# Custom_Made_ESP32_by_Siam_V2.net
KiCad netlist of a schematic drawn in EasyEDA
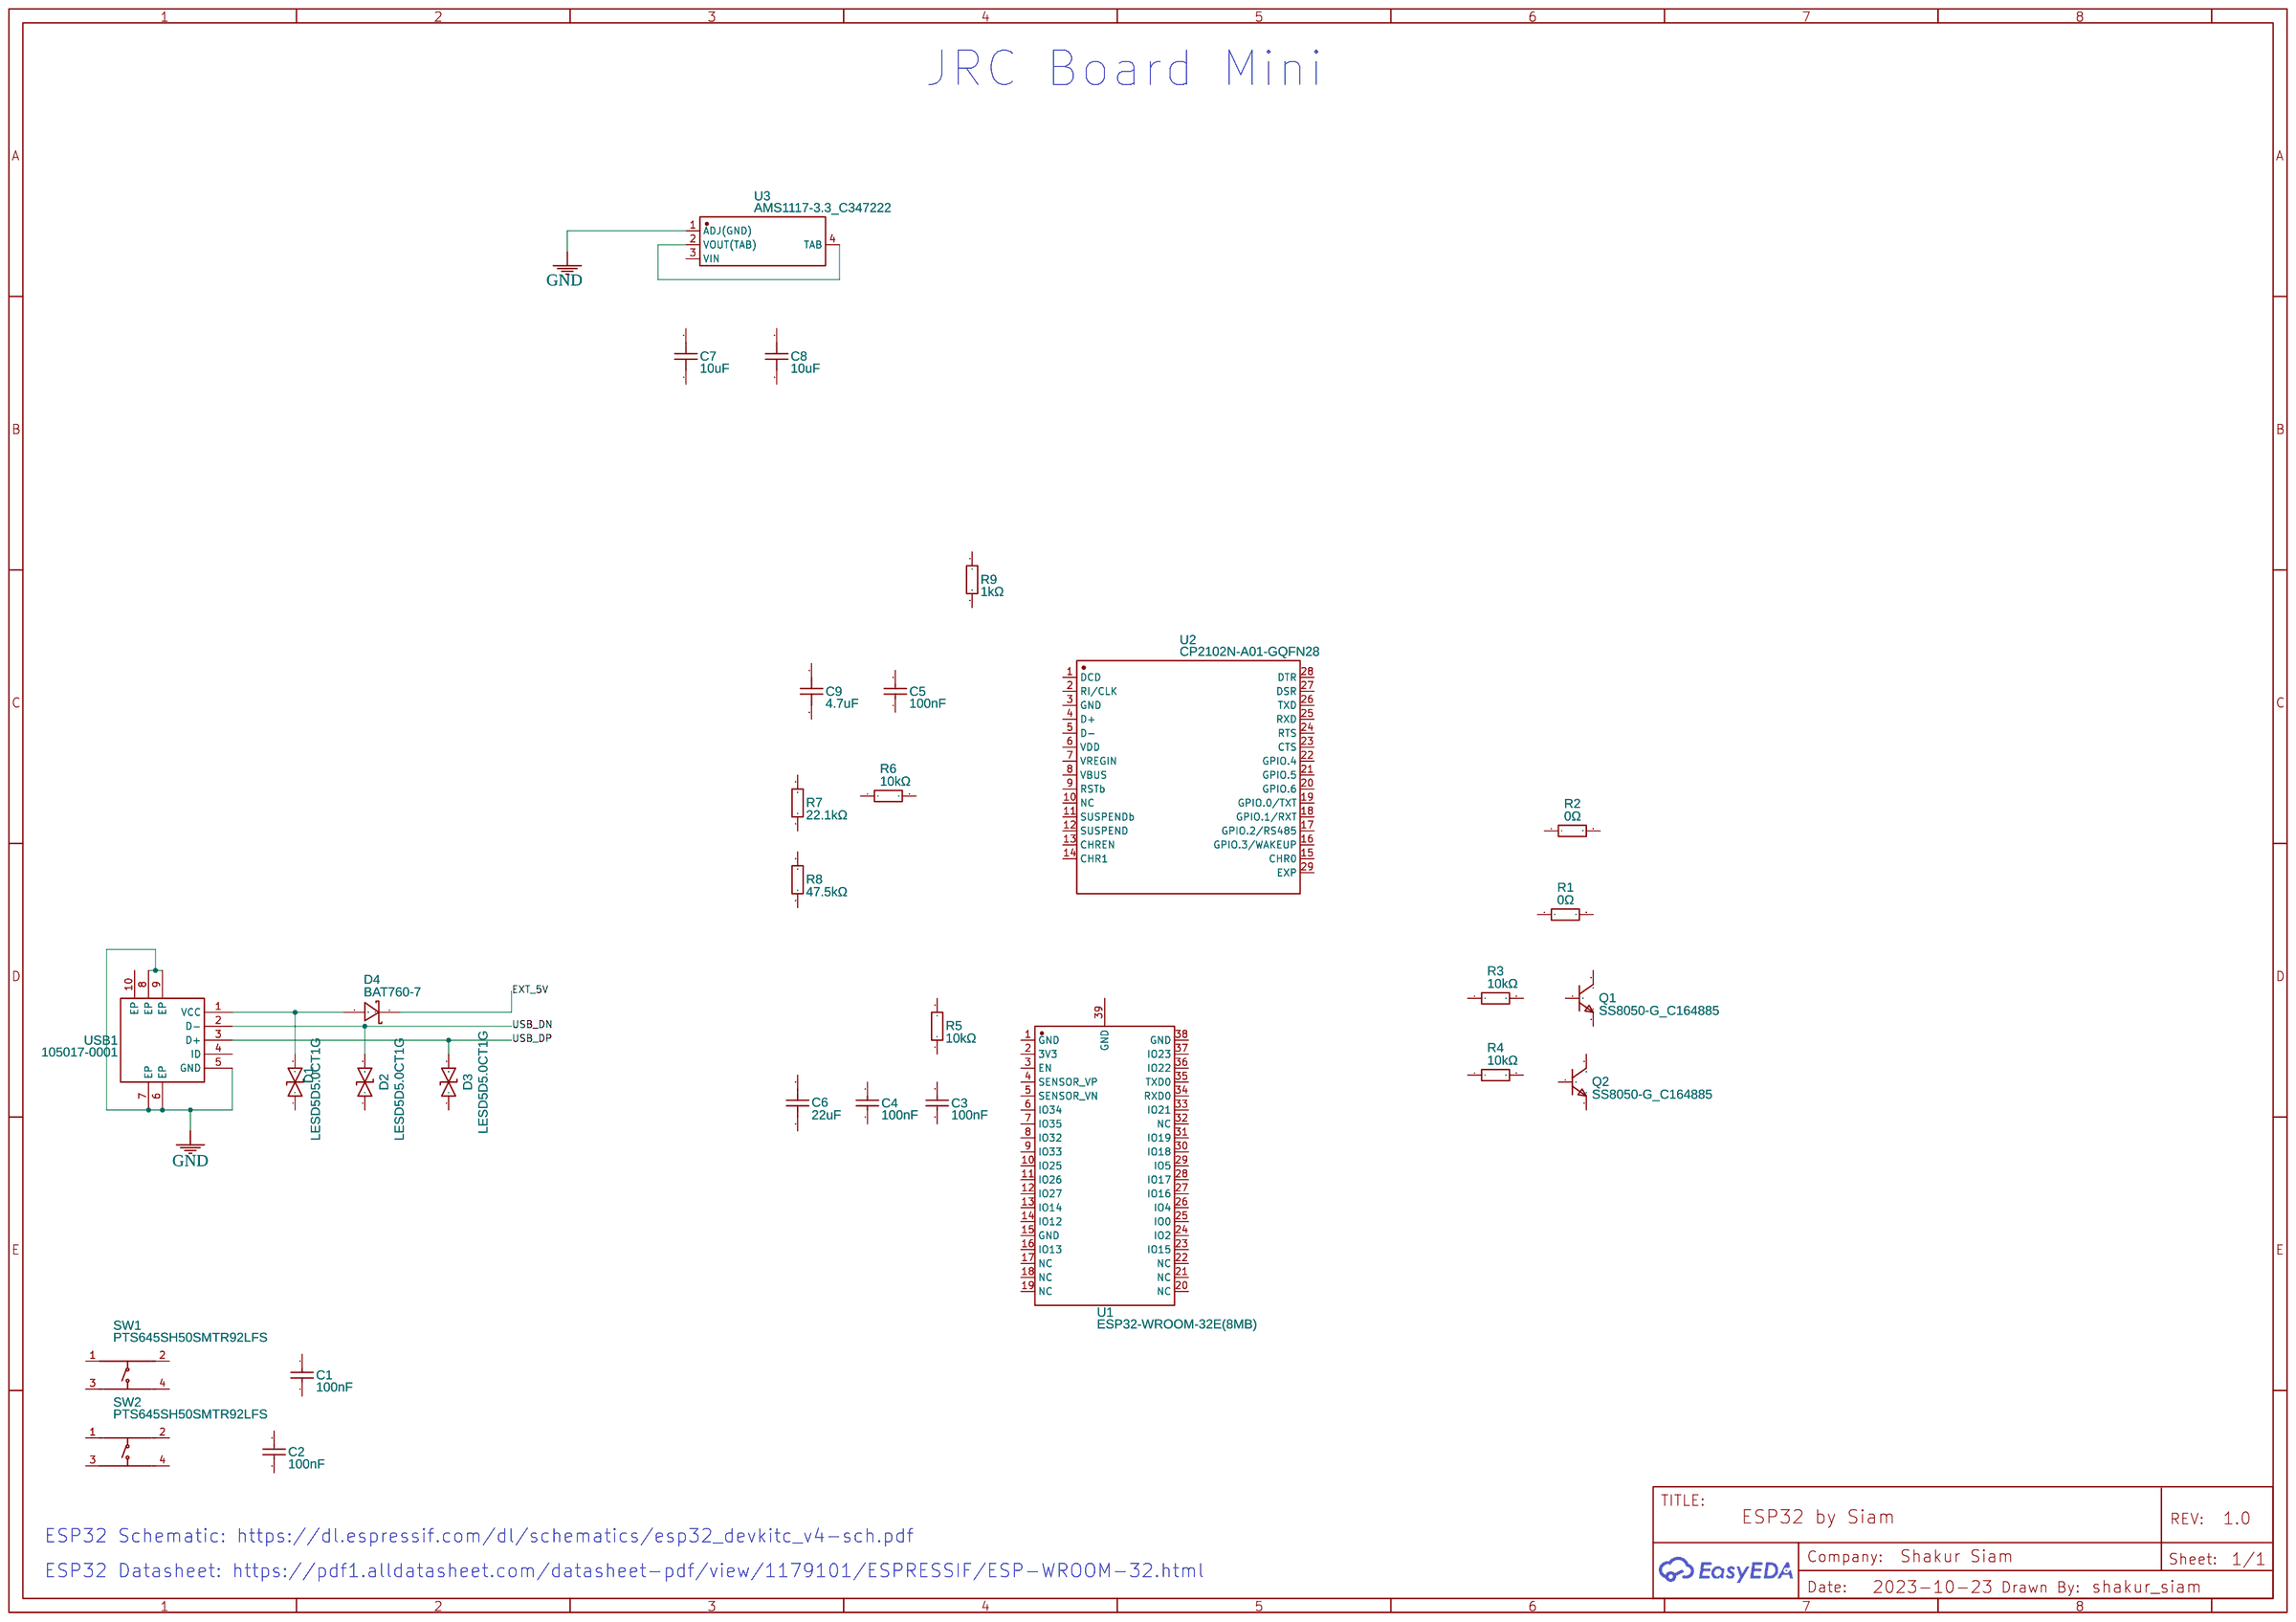
[diagram p0: schematic sheet]

(export (version "E")
  (design (tool "Eeschema 10.0.6"))
  (components
    (comp (ref "C1")
      (value "100nF")
      (fields
        (field (name "Manufacturer Part") "CL05B104KO5NNNC")
        (field (name "Manufacturer") "SAMSUNG(三星)")
      )
      (libsource (lib "") (part "CL05B104KO5NNNC"))
    )
    (comp (ref "C2")
      (value "100nF")
      (fields
        (field (name "Manufacturer Part") "CL05B104KO5NNNC")
        (field (name "Manufacturer") "SAMSUNG(三星)")
      )
      (libsource (lib "") (part "CL05B104KO5NNNC"))
    )
    (comp (ref "C3")
      (value "100nF")
      (fields
        (field (name "Manufacturer Part") "CL05B104KO5NNNC")
        (field (name "Manufacturer") "SAMSUNG(三星)")
      )
      (libsource (lib "") (part "CL05B104KO5NNNC"))
    )
    (comp (ref "C4")
      (value "100nF")
      (fields
        (field (name "Manufacturer Part") "CL05B104KO5NNNC")
        (field (name "Manufacturer") "SAMSUNG(三星)")
      )
      (libsource (lib "") (part "CL05B104KO5NNNC"))
    )
    (comp (ref "C5")
      (value "100nF")
      (fields
        (field (name "Manufacturer Part") "CL05B104KO5NNNC")
        (field (name "Manufacturer") "SAMSUNG(三星)")
      )
      (libsource (lib "") (part "CL05B104KO5NNNC"))
    )
    (comp (ref "C6")
      (value "22uF")
      (fields
        (field (name "Manufacturer Part") "CL21A226MAYNNNE")
        (field (name "Manufacturer") "SAMSUNG(三星)")
      )
      (libsource (lib "") (part "CL21A226MAYNNNE"))
    )
    (comp (ref "C7")
      (value "10uF")
      (fields
        (field (name "Manufacturer Part") "CL05A106MP5NUNC")
        (field (name "Manufacturer") "SAMSUNG(三星)")
      )
      (libsource (lib "") (part "CL05A106MP5NUNC_C315248"))
    )
    (comp (ref "C8")
      (value "10uF")
      (fields
        (field (name "Manufacturer Part") "CL05A106MP5NUNC")
        (field (name "Manufacturer") "SAMSUNG(三星)")
      )
      (libsource (lib "") (part "CL05A106MP5NUNC_C315248"))
    )
    (comp (ref "C9")
      (value "4.7uF")
      (fields
        (field (name "Manufacturer Part") "CL05A475KP5NRNC")
        (field (name "Manufacturer") "SAMSUNG(三星)")
      )
      (libsource (lib "") (part "CL05A475KP5NRNC"))
    )
    (comp (ref "D1")
      (value "LESD5D5.0CT1G")
      (fields (field (name "Manufacturer") "LRC(乐山无线电)"))
      (libsource (lib "") (part "LESD5D5.0CT1G"))
    )
    (comp (ref "D2")
      (value "LESD5D5.0CT1G")
      (fields (field (name "Manufacturer") "LRC(乐山无线电)"))
      (libsource (lib "") (part "LESD5D5.0CT1G"))
    )
    (comp (ref "D3")
      (value "LESD5D5.0CT1G")
      (fields (field (name "Manufacturer") "LRC(乐山无线电)"))
      (libsource (lib "") (part "LESD5D5.0CT1G"))
    )
    (comp (ref "D4")
      (value "BAT760-7")
      (fields (field (name "Manufacturer") "DIODES(美台)"))
      (libsource (lib "") (part "BAT760-7"))
    )
    (comp (ref "Q1")
      (value "SS8050-G_C164885")
      (fields (field (name "Manufacturer Part") "SS8050-G") (field (name "Manufacturer") "CJ(江苏长电/长晶)"))
      (libsource (lib "") (part "SS8050-G_C164885"))
    )
    (comp (ref "Q2")
      (value "SS8050-G_C164885")
      (fields (field (name "Manufacturer Part") "SS8050-G") (field (name "Manufacturer") "CJ(江苏长电/长晶)"))
      (libsource (lib "") (part "SS8050-G_C164885"))
    )
    (comp (ref "R1")
      (value "0Ω")
      (fields
        (field (name "Manufacturer Part") "0402WGF0000TCE")
        (field (name "Manufacturer") "UNI-ROYAL(厚声)")
      )
      (libsource (lib "") (part "0402WGF0000TCE"))
    )
    (comp (ref "R2")
      (value "0Ω")
      (fields
        (field (name "Manufacturer Part") "0402WGF0000TCE")
        (field (name "Manufacturer") "UNI-ROYAL(厚声)")
      )
      (libsource (lib "") (part "0402WGF0000TCE"))
    )
    (comp (ref "R3")
      (value "10kΩ")
      (fields
        (field (name "Manufacturer Part") "0402WGF1002TCE")
        (field (name "Manufacturer") "UNI-ROYAL(厚声)")
      )
      (libsource (lib "") (part "0402WGF1002TCE"))
    )
    (comp (ref "R4")
      (value "10kΩ")
      (fields
        (field (name "Manufacturer Part") "0402WGF1002TCE")
        (field (name "Manufacturer") "UNI-ROYAL(厚声)")
      )
      (libsource (lib "") (part "0402WGF1002TCE"))
    )
    (comp (ref "R5")
      (value "10kΩ")
      (fields
        (field (name "Manufacturer Part") "0402WGF1002TCE")
        (field (name "Manufacturer") "UNI-ROYAL(厚声)")
      )
      (libsource (lib "") (part "0402WGF1002TCE_1"))
    )
    (comp (ref "R6")
      (value "10kΩ")
      (fields
        (field (name "Manufacturer Part") "0402WGF1002TCE")
        (field (name "Manufacturer") "UNI-ROYAL(厚声)")
      )
      (libsource (lib "") (part "0402WGF1002TCE"))
    )
    (comp (ref "R7")
      (value "22.1kΩ")
      (fields
        (field (name "Manufacturer Part") "0402WGF2212TCE")
        (field (name "Manufacturer") "UNI-ROYAL(厚声)")
      )
      (libsource (lib "") (part "0402WGF2212TCE"))
    )
    (comp (ref "R8")
      (value "47.5kΩ")
      (fields
        (field (name "Manufacturer Part") "0402WGF4752TCE")
        (field (name "Manufacturer") "UNI-ROYAL(厚声)")
      )
      (libsource (lib "") (part "0402WGF4752TCE"))
    )
    (comp (ref "R9")
      (value "1kΩ")
      (fields
        (field (name "Manufacturer Part") "0402WGF1001TCE")
        (field (name "Manufacturer") "UNI-ROYAL(厚声)")
      )
      (libsource (lib "") (part "0402WGF1001TCE"))
    )
    (comp (ref "SW1")
      (value "PTS645SH50SMTR92LFS")
      (fields (field (name "Manufacturer") "C&K"))
      (libsource (lib "") (part "PTS645SH50SMTR92LFS"))
    )
    (comp (ref "SW2")
      (value "PTS645SH50SMTR92LFS")
      (fields (field (name "Manufacturer") "C&K"))
      (libsource (lib "") (part "PTS645SH50SMTR92LFS"))
    )
    (comp (ref "U1")
      (value "ESP32-WROOM-32E(8MB)")
      (fields
        (field (name "Manufacturer Part") "ESP32-WROOM-32E-N8")
        (field (name "Manufacturer") "ESPRESSIF(乐鑫)")
      )
      (libsource (lib "") (part "ESP32-WROOM-32E(8MB)"))
    )
    (comp (ref "U2")
      (value "CP2102N-A01-GQFN28")
      (fields
        (field (name "Manufacturer Part") "CP2102N-A01-GQFN28R")
        (field (name "Manufacturer") "SILICON LABS(芯科)")
      )
      (libsource (lib "") (part "CP2102N-A01-GQFN28"))
    )
    (comp (ref "U3")
      (value "AMS1117-3.3_C347222")
      (fields (field (name "Manufacturer Part") "AMS1117-3.3") (field (name "Manufacturer") "UMW(广东友台半导体)"))
      (libsource (lib "") (part "AMS1117-3.3_C347222"))
    )
    (comp (ref "USB1")
      (value "105017-0001")
      (fields (field (name "Manufacturer Part") "1050170001") (field (name "Manufacturer") "MOLEX"))
      (libsource (lib "") (part "105017-0001"))
    )
  )
  (nets
    (net (code "1") (name "/EXT_5V") (class "Default")
      (node (ref "D4") (pin "1") (pinfunction "1_1") (pintype "unspecified"))
    )
    (net (code "2") (name "/USB_DN") (class "Default")
      (node (ref "D2") (pin "2") (pinfunction "2_2") (pintype "unspecified"))
      (node (ref "USB1") (pin "2") (pinfunction "D-_2") (pintype "unspecified"))
    )
    (net (code "3") (name "/USB_DP") (class "Default")
      (node (ref "D3") (pin "2") (pinfunction "2_2") (pintype "unspecified"))
      (node (ref "USB1") (pin "3") (pinfunction "D+_3") (pintype "unspecified"))
    )
    (net (code "4") (name "GND") (class "Default")
      (node (ref "U3") (pin "1") (pinfunction "ADJ(GND)_1") (pintype "unspecified"))
      (node (ref "USB1") (pin "5") (pinfunction "GND_5") (pintype "unspecified"))
      (node (ref "USB1") (pin "6") (pinfunction "EP_6") (pintype "unspecified"))
      (node (ref "USB1") (pin "7") (pinfunction "EP_7") (pintype "unspecified"))
      (node (ref "USB1") (pin "8") (pinfunction "EP_8") (pintype "unspecified"))
      (node (ref "USB1") (pin "9") (pinfunction "EP_9") (pintype "unspecified"))
    )
    (net (code "5") (name "Net-(U3-TAB)") (class "Default")
      (node (ref "U3") (pin "2") (pinfunction "VOUT(TAB)_2") (pintype "unspecified"))
      (node (ref "U3") (pin "4") (pinfunction "TAB_4") (pintype "unspecified"))
    )
    (net (code "6") (name "Net-(USB1-VCC)") (class "Default")
      (node (ref "D1") (pin "2") (pinfunction "2_2") (pintype "unspecified"))
      (node (ref "D4") (pin "2") (pinfunction "2_2") (pintype "unspecified"))
      (node (ref "USB1") (pin "1") (pinfunction "VCC_1") (pintype "unspecified"))
    )
    (net (code "7") (name "unconnected-(C1-Pad1)") (class "Default")
      (node (ref "C1") (pin "1") (pinfunction "1_1") (pintype "input"))
    )
    (net (code "8") (name "unconnected-(C1-Pad2)") (class "Default")
      (node (ref "C1") (pin "2") (pinfunction "2_2") (pintype "input"))
    )
    (net (code "9") (name "unconnected-(C2-Pad1)") (class "Default")
      (node (ref "C2") (pin "1") (pinfunction "1_1") (pintype "input"))
    )
    (net (code "10") (name "unconnected-(C2-Pad2)") (class "Default")
      (node (ref "C2") (pin "2") (pinfunction "2_2") (pintype "input"))
    )
    (net (code "11") (name "unconnected-(C3-Pad1)") (class "Default")
      (node (ref "C3") (pin "1") (pinfunction "1_1") (pintype "input"))
    )
    (net (code "12") (name "unconnected-(C3-Pad2)") (class "Default")
      (node (ref "C3") (pin "2") (pinfunction "2_2") (pintype "input"))
    )
    (net (code "13") (name "unconnected-(C4-Pad1)") (class "Default")
      (node (ref "C4") (pin "1") (pinfunction "1_1") (pintype "input"))
    )
    (net (code "14") (name "unconnected-(C4-Pad2)") (class "Default")
      (node (ref "C4") (pin "2") (pinfunction "2_2") (pintype "input"))
    )
    (net (code "15") (name "unconnected-(C5-Pad1)") (class "Default")
      (node (ref "C5") (pin "1") (pinfunction "1_1") (pintype "input"))
    )
    (net (code "16") (name "unconnected-(C5-Pad2)") (class "Default")
      (node (ref "C5") (pin "2") (pinfunction "2_2") (pintype "input"))
    )
    (net (code "17") (name "unconnected-(C6-Pad1)") (class "Default")
      (node (ref "C6") (pin "1") (pinfunction "1_1") (pintype "unspecified"))
    )
    (net (code "18") (name "unconnected-(C6-Pad2)") (class "Default")
      (node (ref "C6") (pin "2") (pinfunction "2_2") (pintype "unspecified"))
    )
    (net (code "19") (name "unconnected-(C7-Pad1)") (class "Default")
      (node (ref "C7") (pin "1") (pinfunction "1_1") (pintype "unspecified"))
    )
    (net (code "20") (name "unconnected-(C7-Pad2)") (class "Default")
      (node (ref "C7") (pin "2") (pinfunction "2_2") (pintype "unspecified"))
    )
    (net (code "21") (name "unconnected-(C8-Pad1)") (class "Default")
      (node (ref "C8") (pin "1") (pinfunction "1_1") (pintype "unspecified"))
    )
    (net (code "22") (name "unconnected-(C8-Pad2)") (class "Default")
      (node (ref "C8") (pin "2") (pinfunction "2_2") (pintype "unspecified"))
    )
    (net (code "23") (name "unconnected-(C9-Pad1)") (class "Default")
      (node (ref "C9") (pin "1") (pinfunction "1_1") (pintype "unspecified"))
    )
    (net (code "24") (name "unconnected-(C9-Pad2)") (class "Default")
      (node (ref "C9") (pin "2") (pinfunction "2_2") (pintype "unspecified"))
    )
    (net (code "25") (name "unconnected-(D1-Pad1)") (class "Default")
      (node (ref "D1") (pin "1") (pinfunction "1_1") (pintype "unspecified"))
    )
    (net (code "26") (name "unconnected-(D2-Pad1)") (class "Default")
      (node (ref "D2") (pin "1") (pinfunction "1_1") (pintype "unspecified"))
    )
    (net (code "27") (name "unconnected-(D3-Pad1)") (class "Default")
      (node (ref "D3") (pin "1") (pinfunction "1_1") (pintype "unspecified"))
    )
    (net (code "28") (name "unconnected-(Q1-B-Pad1)") (class "Default")
      (node (ref "Q1") (pin "1") (pinfunction "B_1") (pintype "unspecified"))
    )
    (net (code "29") (name "unconnected-(Q1-C-Pad3)") (class "Default")
      (node (ref "Q1") (pin "3") (pinfunction "C_3") (pintype "unspecified"))
    )
    (net (code "30") (name "unconnected-(Q1-E-Pad2)") (class "Default")
      (node (ref "Q1") (pin "2") (pinfunction "E_2") (pintype "unspecified"))
    )
    (net (code "31") (name "unconnected-(Q2-B-Pad1)") (class "Default")
      (node (ref "Q2") (pin "1") (pinfunction "B_1") (pintype "unspecified"))
    )
    (net (code "32") (name "unconnected-(Q2-C-Pad3)") (class "Default")
      (node (ref "Q2") (pin "3") (pinfunction "C_3") (pintype "unspecified"))
    )
    (net (code "33") (name "unconnected-(Q2-E-Pad2)") (class "Default")
      (node (ref "Q2") (pin "2") (pinfunction "E_2") (pintype "unspecified"))
    )
    (net (code "34") (name "unconnected-(R1-Pad1)") (class "Default")
      (node (ref "R1") (pin "1") (pinfunction "1_1") (pintype "input"))
    )
    (net (code "35") (name "unconnected-(R1-Pad2)") (class "Default")
      (node (ref "R1") (pin "2") (pinfunction "2_2") (pintype "input"))
    )
    (net (code "36") (name "unconnected-(R2-Pad1)") (class "Default")
      (node (ref "R2") (pin "1") (pinfunction "1_1") (pintype "input"))
    )
    (net (code "37") (name "unconnected-(R2-Pad2)") (class "Default")
      (node (ref "R2") (pin "2") (pinfunction "2_2") (pintype "input"))
    )
    (net (code "38") (name "unconnected-(R3-Pad1)") (class "Default")
      (node (ref "R3") (pin "1") (pinfunction "1_1") (pintype "input"))
    )
    (net (code "39") (name "unconnected-(R3-Pad2)") (class "Default")
      (node (ref "R3") (pin "2") (pinfunction "2_2") (pintype "input"))
    )
    (net (code "40") (name "unconnected-(R4-Pad1)") (class "Default")
      (node (ref "R4") (pin "1") (pinfunction "1_1") (pintype "input"))
    )
    (net (code "41") (name "unconnected-(R4-Pad2)") (class "Default")
      (node (ref "R4") (pin "2") (pinfunction "2_2") (pintype "input"))
    )
    (net (code "42") (name "unconnected-(R5-Pad1)") (class "Default")
      (node (ref "R5") (pin "1") (pinfunction "1_1") (pintype "input"))
    )
    (net (code "43") (name "unconnected-(R5-Pad2)") (class "Default")
      (node (ref "R5") (pin "2") (pinfunction "2_2") (pintype "input"))
    )
    (net (code "44") (name "unconnected-(R6-Pad1)") (class "Default")
      (node (ref "R6") (pin "1") (pinfunction "1_1") (pintype "input"))
    )
    (net (code "45") (name "unconnected-(R6-Pad2)") (class "Default")
      (node (ref "R6") (pin "2") (pinfunction "2_2") (pintype "input"))
    )
    (net (code "46") (name "unconnected-(R7-Pad1)") (class "Default")
      (node (ref "R7") (pin "1") (pinfunction "1_1") (pintype "input"))
    )
    (net (code "47") (name "unconnected-(R7-Pad2)") (class "Default")
      (node (ref "R7") (pin "2") (pinfunction "2_2") (pintype "input"))
    )
    (net (code "48") (name "unconnected-(R8-Pad1)") (class "Default")
      (node (ref "R8") (pin "1") (pinfunction "1_1") (pintype "input"))
    )
    (net (code "49") (name "unconnected-(R8-Pad2)") (class "Default")
      (node (ref "R8") (pin "2") (pinfunction "2_2") (pintype "input"))
    )
    (net (code "50") (name "unconnected-(R9-Pad1)") (class "Default")
      (node (ref "R9") (pin "1") (pinfunction "1_1") (pintype "input"))
    )
    (net (code "51") (name "unconnected-(R9-Pad2)") (class "Default")
      (node (ref "R9") (pin "2") (pinfunction "2_2") (pintype "input"))
    )
    (net (code "52") (name "unconnected-(SW1-Pad1)") (class "Default")
      (node (ref "SW1") (pin "1") (pinfunction "1_1") (pintype "unspecified"))
    )
    (net (code "53") (name "unconnected-(SW1-Pad2)") (class "Default")
      (node (ref "SW1") (pin "2") (pinfunction "2_2") (pintype "unspecified"))
    )
    (net (code "54") (name "unconnected-(SW1-Pad3)") (class "Default")
      (node (ref "SW1") (pin "3") (pinfunction "3_3") (pintype "unspecified"))
    )
    (net (code "55") (name "unconnected-(SW1-Pad4)") (class "Default")
      (node (ref "SW1") (pin "4") (pinfunction "4_4") (pintype "unspecified"))
    )
    (net (code "56") (name "unconnected-(SW2-Pad1)") (class "Default")
      (node (ref "SW2") (pin "1") (pinfunction "1_1") (pintype "unspecified"))
    )
    (net (code "57") (name "unconnected-(SW2-Pad2)") (class "Default")
      (node (ref "SW2") (pin "2") (pinfunction "2_2") (pintype "unspecified"))
    )
    (net (code "58") (name "unconnected-(SW2-Pad3)") (class "Default")
      (node (ref "SW2") (pin "3") (pinfunction "3_3") (pintype "unspecified"))
    )
    (net (code "59") (name "unconnected-(SW2-Pad4)") (class "Default")
      (node (ref "SW2") (pin "4") (pinfunction "4_4") (pintype "unspecified"))
    )
    (net (code "60") (name "unconnected-(U1-3V3-Pad2)") (class "Default")
      (node (ref "U1") (pin "2") (pinfunction "3V3_2") (pintype "unspecified"))
    )
    (net (code "61") (name "unconnected-(U1-EN-Pad3)") (class "Default")
      (node (ref "U1") (pin "3") (pinfunction "EN_3") (pintype "unspecified"))
    )
    (net (code "62") (name "unconnected-(U1-GND-Pad1)") (class "Default")
      (node (ref "U1") (pin "1") (pinfunction "GND_1") (pintype "unspecified"))
    )
    (net (code "63") (name "unconnected-(U1-GND-Pad15)") (class "Default")
      (node (ref "U1") (pin "15") (pinfunction "GND_15") (pintype "unspecified"))
    )
    (net (code "64") (name "unconnected-(U1-GND-Pad38)") (class "Default")
      (node (ref "U1") (pin "38") (pinfunction "GND_38") (pintype "unspecified"))
    )
    (net (code "65") (name "unconnected-(U1-GND-Pad39)") (class "Default")
      (node (ref "U1") (pin "39") (pinfunction "GND_39") (pintype "unspecified"))
    )
    (net (code "66") (name "unconnected-(U1-IO0-Pad25)") (class "Default")
      (node (ref "U1") (pin "25") (pinfunction "IO0_25") (pintype "unspecified"))
    )
    (net (code "67") (name "unconnected-(U1-IO2-Pad24)") (class "Default")
      (node (ref "U1") (pin "24") (pinfunction "IO2_24") (pintype "unspecified"))
    )
    (net (code "68") (name "unconnected-(U1-IO4-Pad26)") (class "Default")
      (node (ref "U1") (pin "26") (pinfunction "IO4_26") (pintype "unspecified"))
    )
    (net (code "69") (name "unconnected-(U1-IO5-Pad29)") (class "Default")
      (node (ref "U1") (pin "29") (pinfunction "IO5_29") (pintype "unspecified"))
    )
    (net (code "70") (name "unconnected-(U1-IO12-Pad14)") (class "Default")
      (node (ref "U1") (pin "14") (pinfunction "IO12_14") (pintype "unspecified"))
    )
    (net (code "71") (name "unconnected-(U1-IO13-Pad16)") (class "Default")
      (node (ref "U1") (pin "16") (pinfunction "IO13_16") (pintype "unspecified"))
    )
    (net (code "72") (name "unconnected-(U1-IO14-Pad13)") (class "Default")
      (node (ref "U1") (pin "13") (pinfunction "IO14_13") (pintype "unspecified"))
    )
    (net (code "73") (name "unconnected-(U1-IO15-Pad23)") (class "Default")
      (node (ref "U1") (pin "23") (pinfunction "IO15_23") (pintype "unspecified"))
    )
    (net (code "74") (name "unconnected-(U1-IO16-Pad27)") (class "Default")
      (node (ref "U1") (pin "27") (pinfunction "IO16_27") (pintype "unspecified"))
    )
    (net (code "75") (name "unconnected-(U1-IO17-Pad28)") (class "Default")
      (node (ref "U1") (pin "28") (pinfunction "IO17_28") (pintype "unspecified"))
    )
    (net (code "76") (name "unconnected-(U1-IO18-Pad30)") (class "Default")
      (node (ref "U1") (pin "30") (pinfunction "IO18_30") (pintype "unspecified"))
    )
    (net (code "77") (name "unconnected-(U1-IO19-Pad31)") (class "Default")
      (node (ref "U1") (pin "31") (pinfunction "IO19_31") (pintype "unspecified"))
    )
    (net (code "78") (name "unconnected-(U1-IO21-Pad33)") (class "Default")
      (node (ref "U1") (pin "33") (pinfunction "IO21_33") (pintype "unspecified"))
    )
    (net (code "79") (name "unconnected-(U1-IO22-Pad36)") (class "Default")
      (node (ref "U1") (pin "36") (pinfunction "IO22_36") (pintype "unspecified"))
    )
    (net (code "80") (name "unconnected-(U1-IO23-Pad37)") (class "Default")
      (node (ref "U1") (pin "37") (pinfunction "IO23_37") (pintype "unspecified"))
    )
    (net (code "81") (name "unconnected-(U1-IO25-Pad10)") (class "Default")
      (node (ref "U1") (pin "10") (pinfunction "IO25_10") (pintype "unspecified"))
    )
    (net (code "82") (name "unconnected-(U1-IO26-Pad11)") (class "Default")
      (node (ref "U1") (pin "11") (pinfunction "IO26_11") (pintype "unspecified"))
    )
    (net (code "83") (name "unconnected-(U1-IO27-Pad12)") (class "Default")
      (node (ref "U1") (pin "12") (pinfunction "IO27_12") (pintype "unspecified"))
    )
    (net (code "84") (name "unconnected-(U1-IO32-Pad8)") (class "Default")
      (node (ref "U1") (pin "8") (pinfunction "IO32_8") (pintype "unspecified"))
    )
    (net (code "85") (name "unconnected-(U1-IO33-Pad9)") (class "Default")
      (node (ref "U1") (pin "9") (pinfunction "IO33_9") (pintype "unspecified"))
    )
    (net (code "86") (name "unconnected-(U1-IO34-Pad6)") (class "Default")
      (node (ref "U1") (pin "6") (pinfunction "IO34_6") (pintype "unspecified"))
    )
    (net (code "87") (name "unconnected-(U1-IO35-Pad7)") (class "Default")
      (node (ref "U1") (pin "7") (pinfunction "IO35_7") (pintype "unspecified"))
    )
    (net (code "88") (name "unconnected-(U1-NC-Pad17)") (class "Default")
      (node (ref "U1") (pin "17") (pinfunction "NC_17") (pintype "unspecified"))
    )
    (net (code "89") (name "unconnected-(U1-NC-Pad18)") (class "Default")
      (node (ref "U1") (pin "18") (pinfunction "NC_18") (pintype "unspecified"))
    )
    (net (code "90") (name "unconnected-(U1-NC-Pad19)") (class "Default")
      (node (ref "U1") (pin "19") (pinfunction "NC_19") (pintype "unspecified"))
    )
    (net (code "91") (name "unconnected-(U1-NC-Pad20)") (class "Default")
      (node (ref "U1") (pin "20") (pinfunction "NC_20") (pintype "unspecified"))
    )
    (net (code "92") (name "unconnected-(U1-NC-Pad21)") (class "Default")
      (node (ref "U1") (pin "21") (pinfunction "NC_21") (pintype "unspecified"))
    )
    (net (code "93") (name "unconnected-(U1-NC-Pad22)") (class "Default")
      (node (ref "U1") (pin "22") (pinfunction "NC_22") (pintype "unspecified"))
    )
    (net (code "94") (name "unconnected-(U1-NC-Pad32)") (class "Default")
      (node (ref "U1") (pin "32") (pinfunction "NC_32") (pintype "unspecified"))
    )
    (net (code "95") (name "unconnected-(U1-RXD0-Pad34)") (class "Default")
      (node (ref "U1") (pin "34") (pinfunction "RXD0_34") (pintype "unspecified"))
    )
    (net (code "96") (name "unconnected-(U1-SENSOR_VN-Pad5)") (class "Default")
      (node (ref "U1") (pin "5") (pinfunction "SENSOR_VN_5") (pintype "unspecified"))
    )
    (net (code "97") (name "unconnected-(U1-SENSOR_VP-Pad4)") (class "Default")
      (node (ref "U1") (pin "4") (pinfunction "SENSOR_VP_4") (pintype "unspecified"))
    )
    (net (code "98") (name "unconnected-(U1-TXD0-Pad35)") (class "Default")
      (node (ref "U1") (pin "35") (pinfunction "TXD0_35") (pintype "unspecified"))
    )
    (net (code "99") (name "unconnected-(U2-CHR0-Pad15)") (class "Default")
      (node (ref "U2") (pin "15") (pinfunction "CHR0_15") (pintype "unspecified"))
    )
    (net (code "100") (name "unconnected-(U2-CHR1-Pad14)") (class "Default")
      (node (ref "U2") (pin "14") (pinfunction "CHR1_14") (pintype "unspecified"))
    )
    (net (code "101") (name "unconnected-(U2-CHREN-Pad13)") (class "Default")
      (node (ref "U2") (pin "13") (pinfunction "CHREN_13") (pintype "unspecified"))
    )
    (net (code "102") (name "unconnected-(U2-CTS-Pad23)") (class "Default")
      (node (ref "U2") (pin "23") (pinfunction "CTS_23") (pintype "unspecified"))
    )
    (net (code "103") (name "unconnected-(U2-D+-Pad4)") (class "Default")
      (node (ref "U2") (pin "4") (pinfunction "D+_4") (pintype "unspecified"))
    )
    (net (code "104") (name "unconnected-(U2-D--Pad5)") (class "Default")
      (node (ref "U2") (pin "5") (pinfunction "D-_5") (pintype "unspecified"))
    )
    (net (code "105") (name "unconnected-(U2-DCD-Pad1)") (class "Default")
      (node (ref "U2") (pin "1") (pinfunction "DCD_1") (pintype "unspecified"))
    )
    (net (code "106") (name "unconnected-(U2-DSR-Pad27)") (class "Default")
      (node (ref "U2") (pin "27") (pinfunction "DSR_27") (pintype "unspecified"))
    )
    (net (code "107") (name "unconnected-(U2-DTR-Pad28)") (class "Default")
      (node (ref "U2") (pin "28") (pinfunction "DTR_28") (pintype "unspecified"))
    )
    (net (code "108") (name "unconnected-(U2-EXP-Pad29)") (class "Default")
      (node (ref "U2") (pin "29") (pinfunction "EXP_29") (pintype "unspecified"))
    )
    (net (code "109") (name "unconnected-(U2-GND-Pad3)") (class "Default")
      (node (ref "U2") (pin "3") (pinfunction "GND_3") (pintype "unspecified"))
    )
    (net (code "110") (name "unconnected-(U2-GPIO.0{slash}TXT-Pad19)") (class "Default")
      (node (ref "U2") (pin "19") (pinfunction "GPIO.0/TXT_19") (pintype "unspecified"))
    )
    (net (code "111") (name "unconnected-(U2-GPIO.1{slash}RXT-Pad18)") (class "Default")
      (node (ref "U2") (pin "18") (pinfunction "GPIO.1/RXT_18") (pintype "unspecified"))
    )
    (net (code "112") (name "unconnected-(U2-GPIO.2{slash}RS485-Pad17)") (class "Default")
      (node (ref "U2") (pin "17") (pinfunction "GPIO.2/RS485_17") (pintype "unspecified"))
    )
    (net (code "113") (name "unconnected-(U2-GPIO.3{slash}WAKEUP-Pad16)") (class "Default")
      (node (ref "U2") (pin "16") (pinfunction "GPIO.3/WAKEUP_16") (pintype "unspecified"))
    )
    (net (code "114") (name "unconnected-(U2-GPIO.4-Pad22)") (class "Default")
      (node (ref "U2") (pin "22") (pinfunction "GPIO.4_22") (pintype "unspecified"))
    )
    (net (code "115") (name "unconnected-(U2-GPIO.5-Pad21)") (class "Default")
      (node (ref "U2") (pin "21") (pinfunction "GPIO.5_21") (pintype "unspecified"))
    )
    (net (code "116") (name "unconnected-(U2-GPIO.6-Pad20)") (class "Default")
      (node (ref "U2") (pin "20") (pinfunction "GPIO.6_20") (pintype "unspecified"))
    )
    (net (code "117") (name "unconnected-(U2-NC-Pad10)") (class "Default")
      (node (ref "U2") (pin "10") (pinfunction "NC_10") (pintype "unspecified"))
    )
    (net (code "118") (name "unconnected-(U2-RI{slash}CLK-Pad2)") (class "Default")
      (node (ref "U2") (pin "2") (pinfunction "RI/CLK_2") (pintype "unspecified"))
    )
    (net (code "119") (name "unconnected-(U2-RSTb-Pad9)") (class "Default")
      (node (ref "U2") (pin "9") (pinfunction "RSTb_9") (pintype "unspecified"))
    )
    (net (code "120") (name "unconnected-(U2-RTS-Pad24)") (class "Default")
      (node (ref "U2") (pin "24") (pinfunction "RTS_24") (pintype "unspecified"))
    )
    (net (code "121") (name "unconnected-(U2-RXD-Pad25)") (class "Default")
      (node (ref "U2") (pin "25") (pinfunction "RXD_25") (pintype "unspecified"))
    )
    (net (code "122") (name "unconnected-(U2-SUSPEND-Pad12)") (class "Default")
      (node (ref "U2") (pin "12") (pinfunction "SUSPEND_12") (pintype "unspecified"))
    )
    (net (code "123") (name "unconnected-(U2-SUSPENDb-Pad11)") (class "Default")
      (node (ref "U2") (pin "11") (pinfunction "SUSPENDb_11") (pintype "unspecified"))
    )
    (net (code "124") (name "unconnected-(U2-TXD-Pad26)") (class "Default")
      (node (ref "U2") (pin "26") (pinfunction "TXD_26") (pintype "unspecified"))
    )
    (net (code "125") (name "unconnected-(U2-VBUS-Pad8)") (class "Default")
      (node (ref "U2") (pin "8") (pinfunction "VBUS_8") (pintype "unspecified"))
    )
    (net (code "126") (name "unconnected-(U2-VDD-Pad6)") (class "Default")
      (node (ref "U2") (pin "6") (pinfunction "VDD_6") (pintype "unspecified"))
    )
    (net (code "127") (name "unconnected-(U2-VREGIN-Pad7)") (class "Default")
      (node (ref "U2") (pin "7") (pinfunction "VREGIN_7") (pintype "unspecified"))
    )
    (net (code "128") (name "unconnected-(U3-VIN-Pad3)") (class "Default")
      (node (ref "U3") (pin "3") (pinfunction "VIN_3") (pintype "unspecified"))
    )
    (net (code "129") (name "unconnected-(USB1-EP-Pad10)") (class "Default")
      (node (ref "USB1") (pin "10") (pinfunction "EP_10") (pintype "unspecified"))
    )
    (net (code "130") (name "unconnected-(USB1-ID-Pad4)") (class "Default")
      (node (ref "USB1") (pin "4") (pinfunction "ID_4") (pintype "unspecified"))
    )
  )
)
